# MotorChip.net
KiCad netlist of a schematic drawn in EAGLE
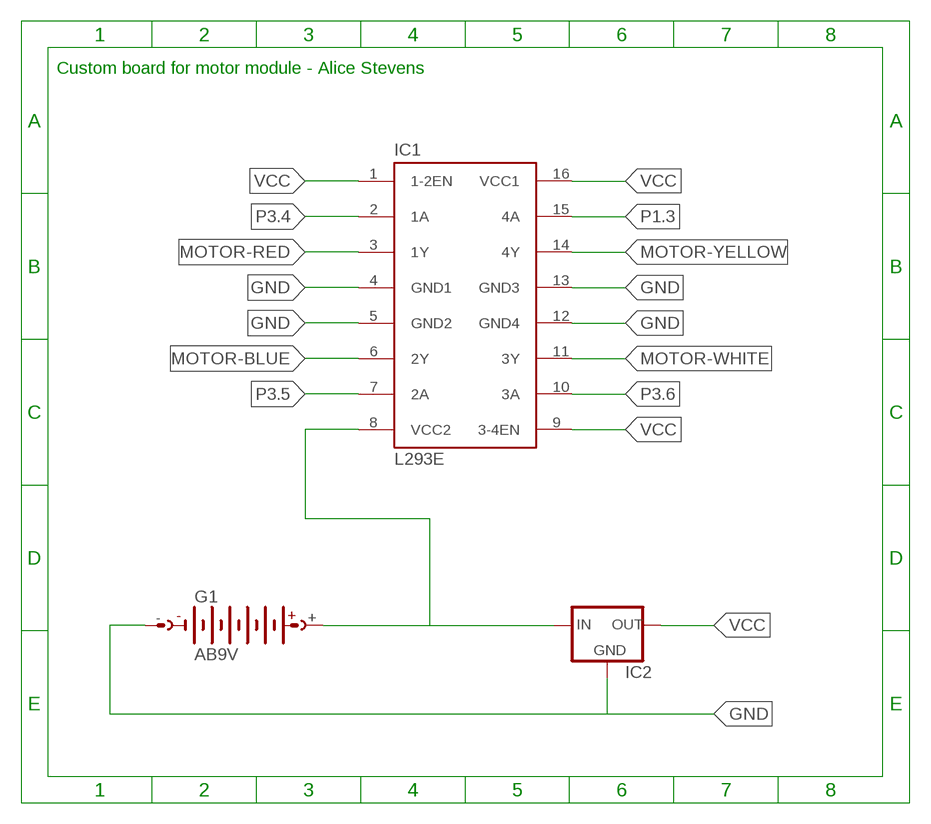
[diagram p0: schematic, sheet 1]

(export (version "E")
  (design (tool "Eeschema 10.0.6"))
  (components
    (comp (ref "G1")
      (value "AB9V")
      (footprint "eagle-import:AB9V")
      (libsource (lib "eagle-import") (part "AB9V"))
    )
    (comp (ref "IC1")
      (value "L293E")
      (footprint "eagle-import:DIL16")
      (fields (field (name "MF") "Arrow Electronics"))
      (libsource (lib "eagle-import") (part "L293E"))
    )
    (comp (ref "IC2")
      (value "78XXL")
      (footprint "eagle-import:78XXL")
      (libsource (lib "eagle-import") (part "78XXL"))
    )
  )
  (nets
    (net (code "1") (name "GND") (class "Default")
      (node (ref "G1") (pin "-") (pinfunction "-_-") (pintype "passive"))
      (node (ref "IC1") (pin "12") (pinfunction "GND4_12") (pintype "power_in"))
      (node (ref "IC1") (pin "13") (pinfunction "GND3_13") (pintype "power_in"))
      (node (ref "IC1") (pin "4") (pinfunction "GND1_4") (pintype "power_in"))
      (node (ref "IC1") (pin "5") (pinfunction "GND2_5") (pintype "power_in"))
      (node (ref "IC2") (pin "GND") (pinfunction "GND_GND") (pintype "input"))
    )
    (net (code "2") (name "MOTOR-BLUE") (class "Default")
      (node (ref "IC1") (pin "6") (pinfunction "2Y_6") (pintype "output"))
    )
    (net (code "3") (name "MOTOR-RED") (class "Default")
      (node (ref "IC1") (pin "3") (pinfunction "1Y_3") (pintype "output"))
    )
    (net (code "4") (name "MOTOR-WHITE") (class "Default")
      (node (ref "IC1") (pin "11") (pinfunction "3Y_11") (pintype "output"))
    )
    (net (code "5") (name "MOTOR-YELLOW") (class "Default")
      (node (ref "IC1") (pin "14") (pinfunction "4Y_14") (pintype "output"))
    )
    (net (code "6") (name "Net-(IC1-VCC2)") (class "Default")
      (node (ref "G1") (pin "+") (pinfunction "+_+") (pintype "passive"))
      (node (ref "IC1") (pin "8") (pinfunction "VCC2_8") (pintype "power_in"))
      (node (ref "IC2") (pin "IN") (pinfunction "IN_IN") (pintype "input"))
    )
    (net (code "7") (name "P1.3") (class "Default")
      (node (ref "IC1") (pin "15") (pinfunction "4A_15") (pintype "input"))
    )
    (net (code "8") (name "P3.4") (class "Default")
      (node (ref "IC1") (pin "2") (pinfunction "1A_2") (pintype "input"))
    )
    (net (code "9") (name "P3.5") (class "Default")
      (node (ref "IC1") (pin "7") (pinfunction "2A_7") (pintype "input"))
    )
    (net (code "10") (name "P3.6") (class "Default")
      (node (ref "IC1") (pin "10") (pinfunction "3A_10") (pintype "input"))
    )
    (net (code "11") (name "VCC") (class "Default")
      (node (ref "IC1") (pin "1") (pinfunction "1-2EN_1") (pintype "input"))
      (node (ref "IC1") (pin "16") (pinfunction "VCC1_16") (pintype "power_in"))
      (node (ref "IC1") (pin "9") (pinfunction "3-4EN_9") (pintype "input"))
      (node (ref "IC2") (pin "OUT") (pinfunction "OUT_OUT") (pintype "passive"))
    )
  )
)
